# M221D.net
KiCad netlist of a schematic drawn in EAGLE
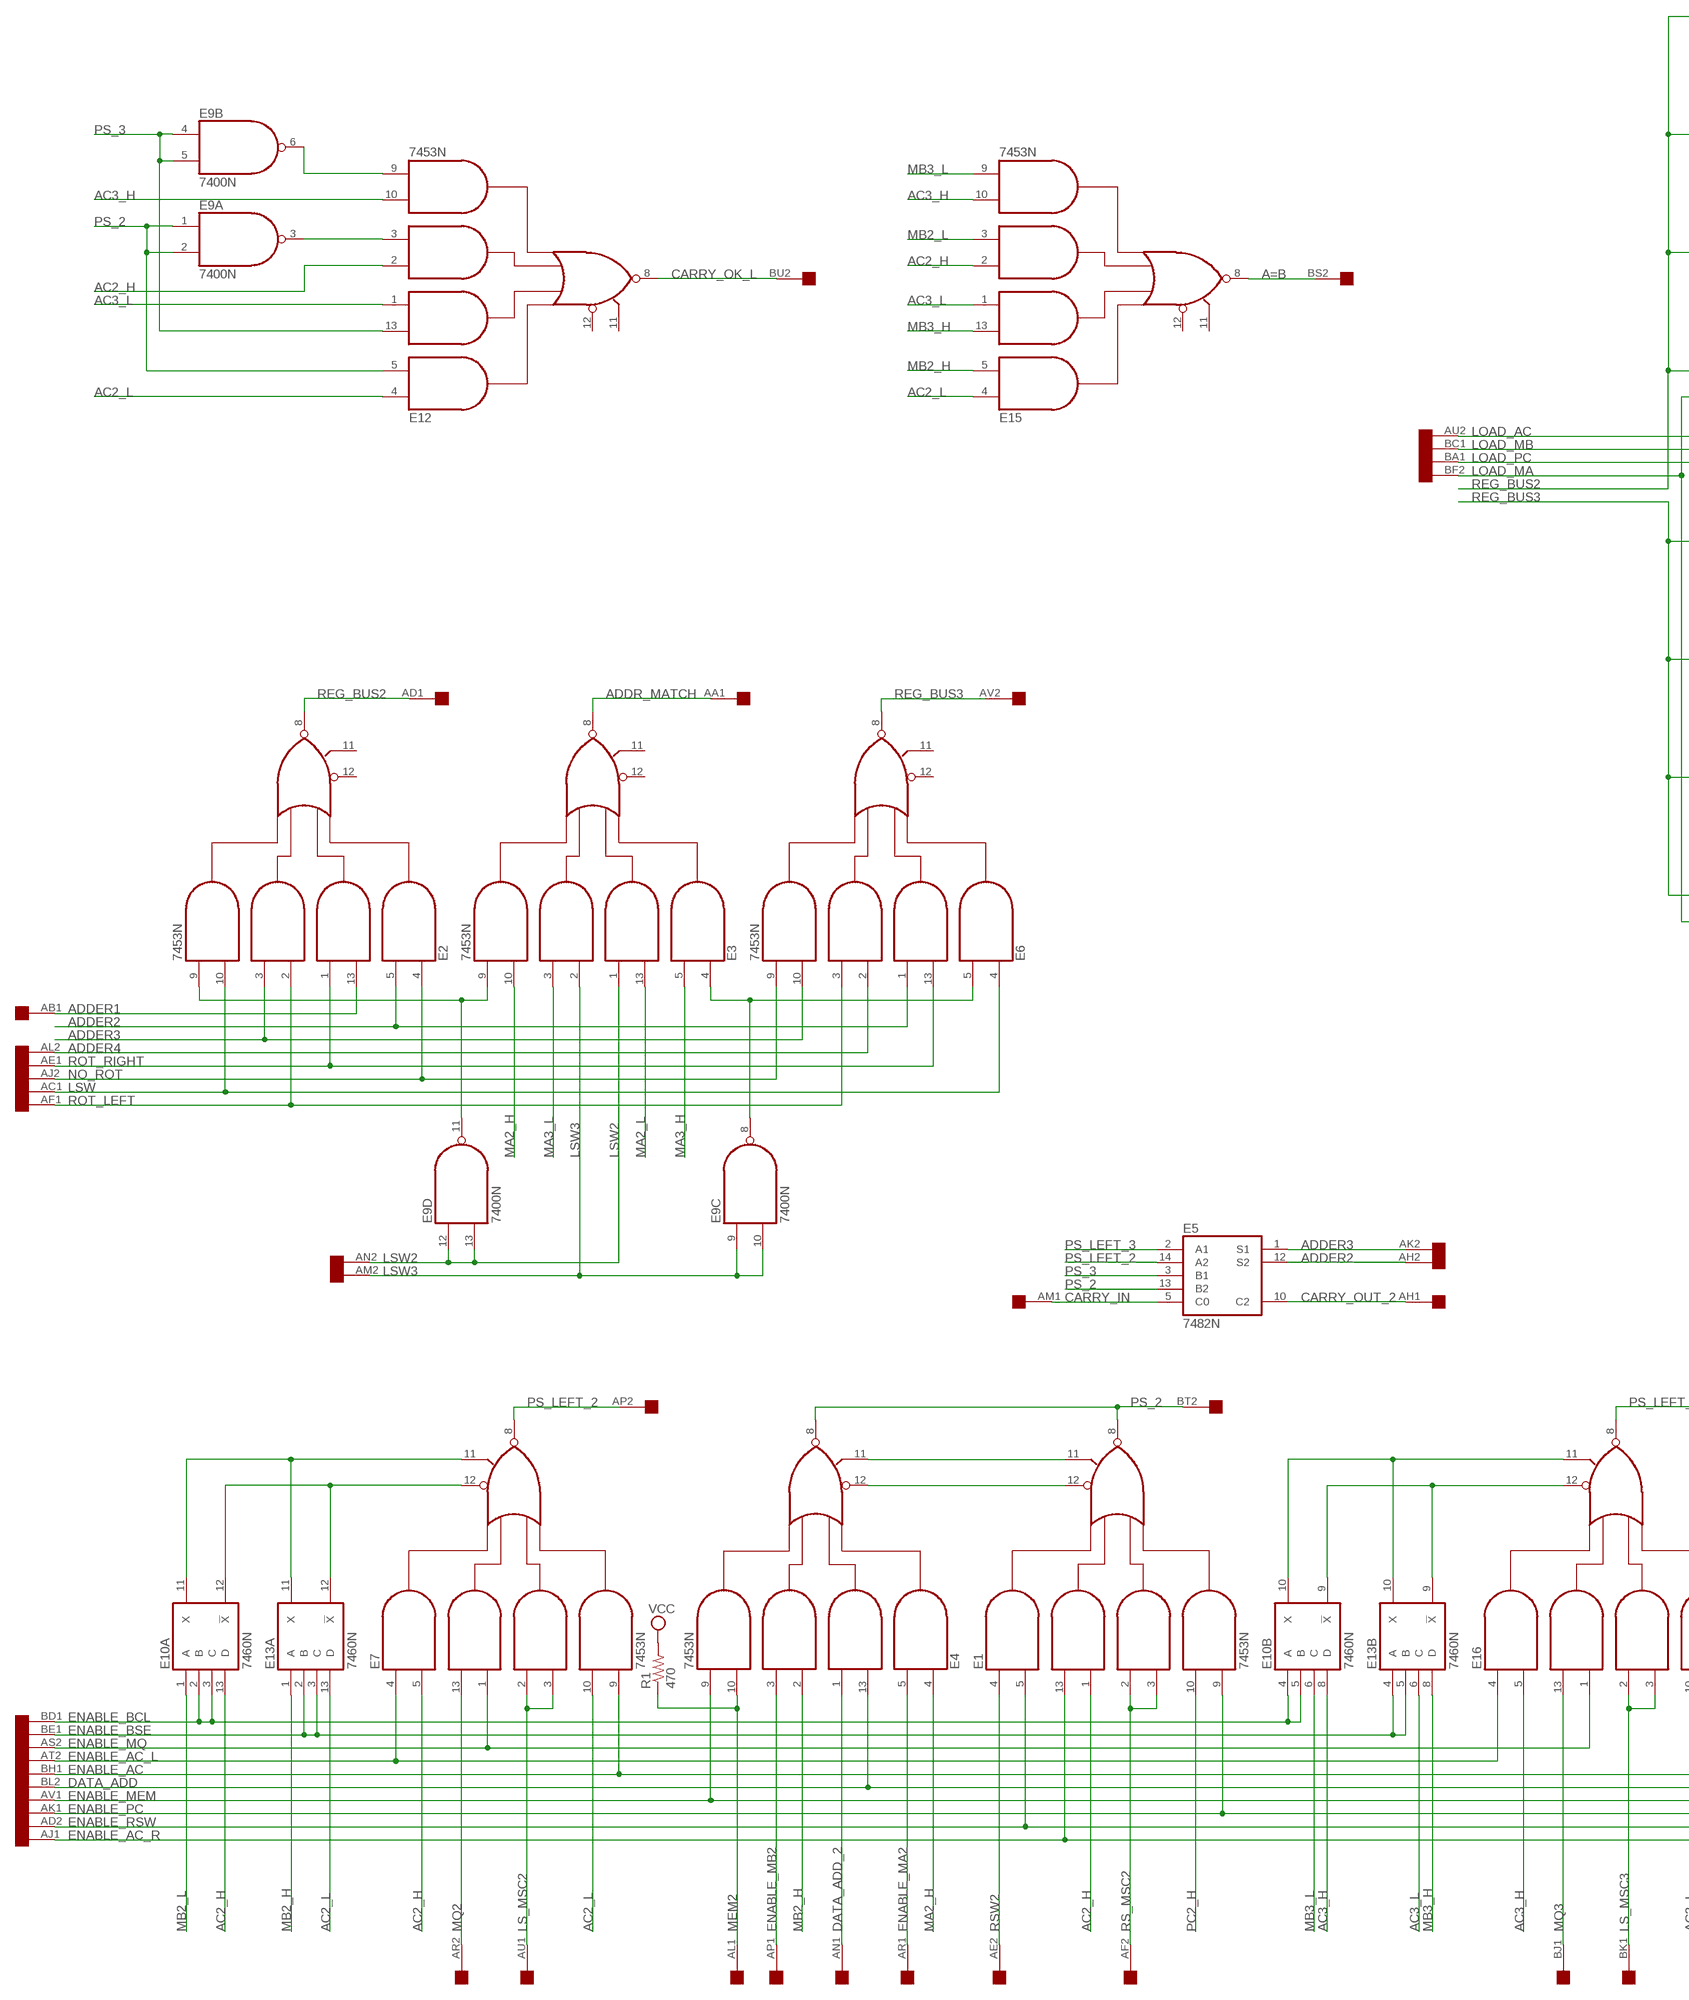
[diagram p0: schematic, sheet 1, part 1 of 2]
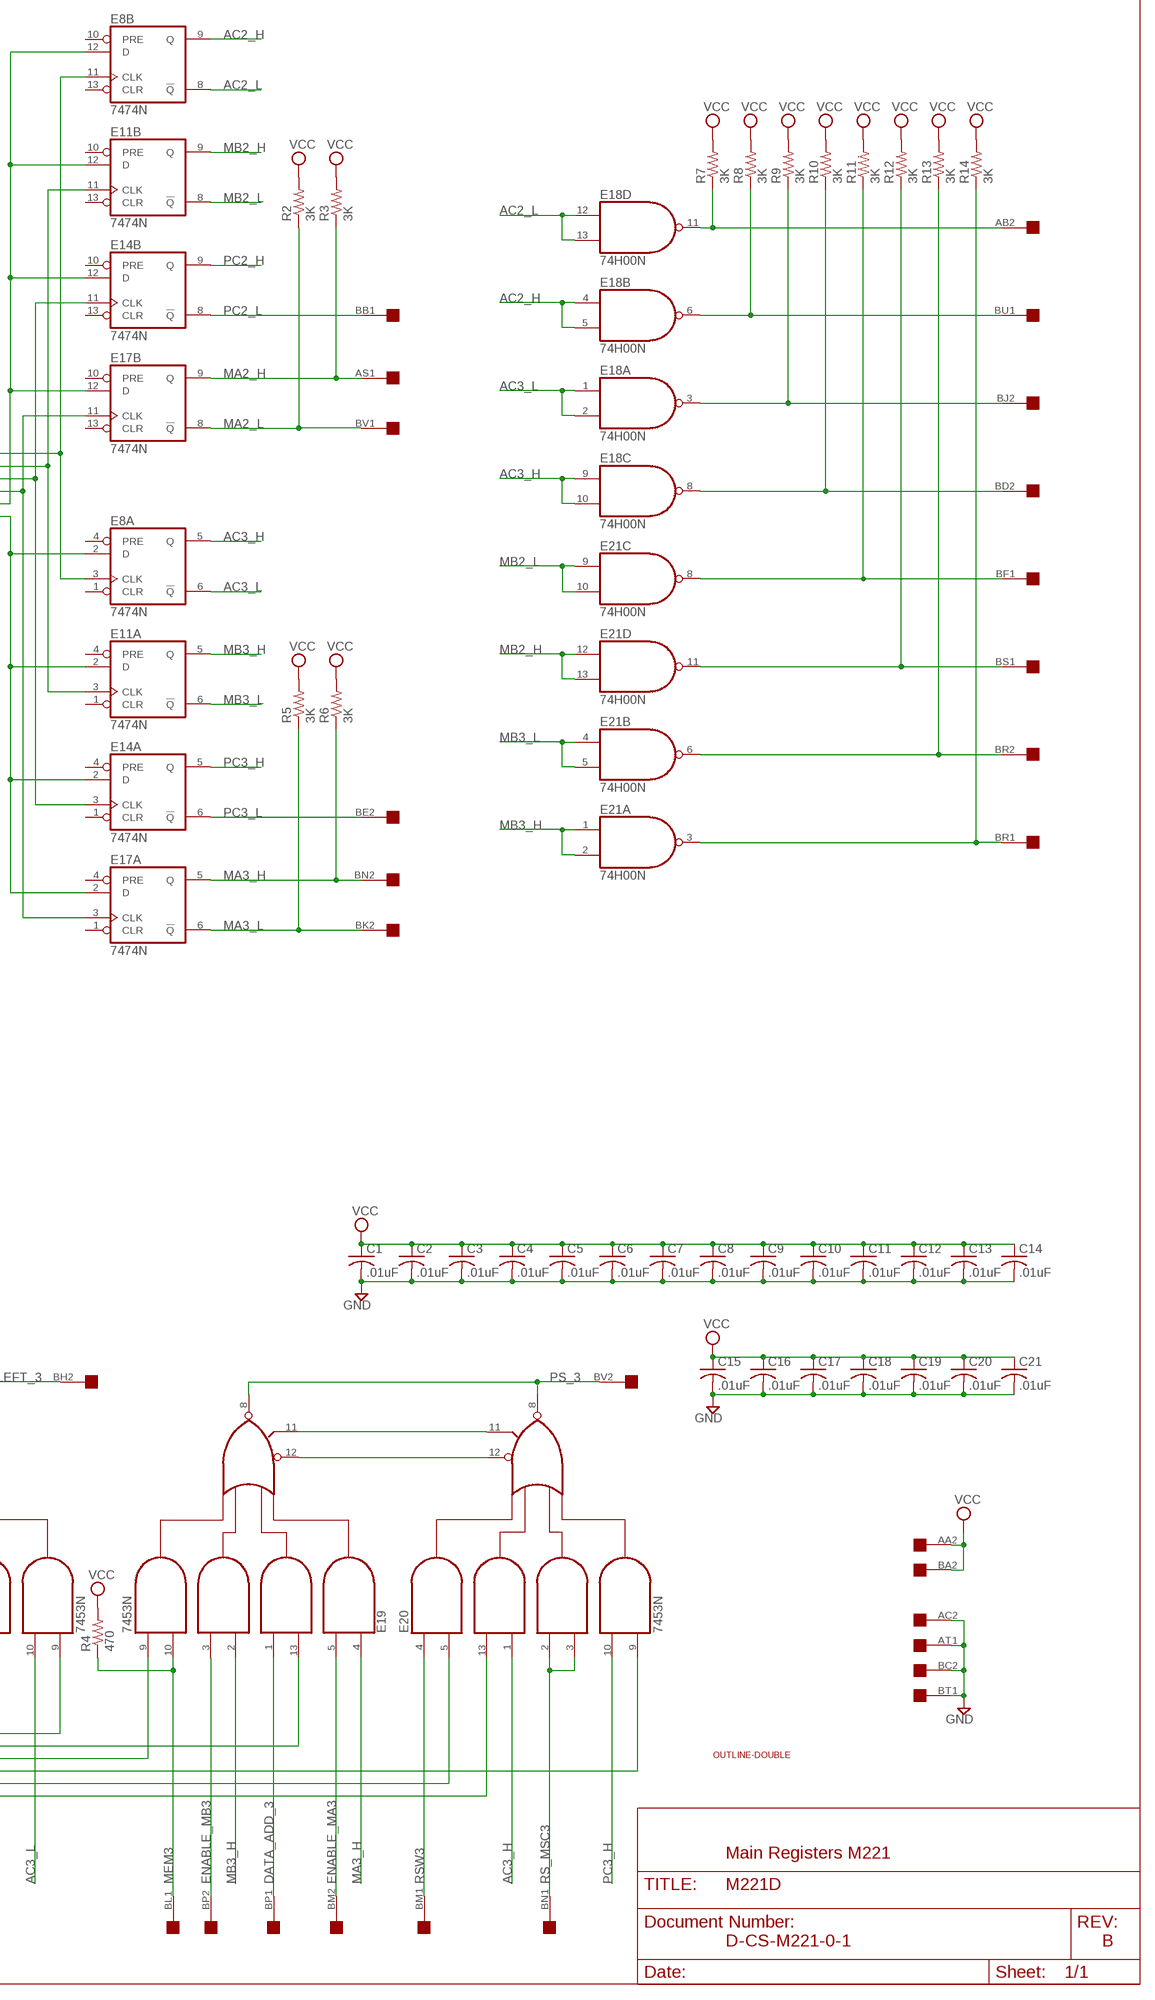
[diagram p1: schematic, sheet 1, part 2 of 2]

(export (version "E")
  (design (tool "Eeschema 10.0.6"))
  (components
    (comp (ref "C1")
      (value ".01uF")
      (footprint "eagle-import:C050-025X075")
      (libsource (lib "eagle-import") (part "C-US050-025X075"))
    )
    (comp (ref "C2")
      (value ".01uF")
      (footprint "eagle-import:C050-025X075")
      (libsource (lib "eagle-import") (part "C-US050-025X075"))
    )
    (comp (ref "C3")
      (value ".01uF")
      (footprint "eagle-import:C050-025X075")
      (libsource (lib "eagle-import") (part "C-US050-025X075"))
    )
    (comp (ref "C4")
      (value ".01uF")
      (footprint "eagle-import:C050-025X075")
      (libsource (lib "eagle-import") (part "C-US050-025X075"))
    )
    (comp (ref "C5")
      (value ".01uF")
      (footprint "eagle-import:C050-025X075")
      (libsource (lib "eagle-import") (part "C-US050-025X075"))
    )
    (comp (ref "C6")
      (value ".01uF")
      (footprint "eagle-import:C050-025X075")
      (libsource (lib "eagle-import") (part "C-US050-025X075"))
    )
    (comp (ref "C7")
      (value ".01uF")
      (footprint "eagle-import:C050-025X075")
      (libsource (lib "eagle-import") (part "C-US050-025X075"))
    )
    (comp (ref "C8")
      (value ".01uF")
      (footprint "eagle-import:C050-025X075")
      (libsource (lib "eagle-import") (part "C-US050-025X075"))
    )
    (comp (ref "C9")
      (value ".01uF")
      (footprint "eagle-import:C050-025X075")
      (libsource (lib "eagle-import") (part "C-US050-025X075"))
    )
    (comp (ref "C10")
      (value ".01uF")
      (footprint "eagle-import:C050-025X075")
      (libsource (lib "eagle-import") (part "C-US050-025X075"))
    )
    (comp (ref "C11")
      (value ".01uF")
      (footprint "eagle-import:C050-025X075")
      (libsource (lib "eagle-import") (part "C-US050-025X075"))
    )
    (comp (ref "C12")
      (value ".01uF")
      (footprint "eagle-import:C050-025X075")
      (libsource (lib "eagle-import") (part "C-US050-025X075"))
    )
    (comp (ref "C13")
      (value ".01uF")
      (footprint "eagle-import:C050-025X075")
      (libsource (lib "eagle-import") (part "C-US050-025X075"))
    )
    (comp (ref "C14")
      (value ".01uF")
      (footprint "eagle-import:C050-025X075")
      (libsource (lib "eagle-import") (part "C-US050-025X075"))
    )
    (comp (ref "C15")
      (value ".01uF")
      (footprint "eagle-import:C050-025X075")
      (libsource (lib "eagle-import") (part "C-US050-025X075"))
    )
    (comp (ref "C16")
      (value ".01uF")
      (footprint "eagle-import:C050-025X075")
      (libsource (lib "eagle-import") (part "C-US050-025X075"))
    )
    (comp (ref "C17")
      (value ".01uF")
      (footprint "eagle-import:C050-025X075")
      (libsource (lib "eagle-import") (part "C-US050-025X075"))
    )
    (comp (ref "C18")
      (value ".01uF")
      (footprint "eagle-import:C050-025X075")
      (libsource (lib "eagle-import") (part "C-US050-025X075"))
    )
    (comp (ref "C19")
      (value ".01uF")
      (footprint "eagle-import:C050-025X075")
      (libsource (lib "eagle-import") (part "C-US050-025X075"))
    )
    (comp (ref "C20")
      (value ".01uF")
      (footprint "eagle-import:C050-025X075")
      (libsource (lib "eagle-import") (part "C-US050-025X075"))
    )
    (comp (ref "C21")
      (value ".01uF")
      (footprint "eagle-import:C050-025X075")
      (libsource (lib "eagle-import") (part "C-US050-025X075"))
    )
    (comp (ref "E1")
      (value "7453N")
      (footprint "eagle-import:DIL14")
      (libsource (lib "eagle-import") (part "7453N"))
    )
    (comp (ref "E2")
      (value "7453N")
      (footprint "eagle-import:DIL14")
      (libsource (lib "eagle-import") (part "7453N"))
    )
    (comp (ref "E3")
      (value "7453N")
      (footprint "eagle-import:DIL14")
      (libsource (lib "eagle-import") (part "7453N"))
    )
    (comp (ref "E4")
      (value "7453N")
      (footprint "eagle-import:DIL14")
      (libsource (lib "eagle-import") (part "7453N"))
    )
    (comp (ref "E5")
      (value "7482N")
      (footprint "eagle-import:DIL14")
      (libsource (lib "eagle-import") (part "7482N"))
    )
    (comp (ref "E6")
      (value "7453N")
      (footprint "eagle-import:DIL14")
      (libsource (lib "eagle-import") (part "7453N"))
    )
    (comp (ref "E7")
      (value "7453N")
      (footprint "eagle-import:DIL14")
      (libsource (lib "eagle-import") (part "7453N"))
    )
    (comp (ref "E8")
      (value "7474N")
      (footprint "eagle-import:DIL14")
      (libsource (lib "eagle-import") (part "7474NS"))
    )
    (comp (ref "E9")
      (value "7400N")
      (footprint "eagle-import:DIL14")
      (libsource (lib "eagle-import") (part "7400N"))
    )
    (comp (ref "E10")
      (value "7460N")
      (footprint "eagle-import:DIL14")
      (libsource (lib "eagle-import") (part "7460N"))
    )
    (comp (ref "E11")
      (value "7474N")
      (footprint "eagle-import:DIL14")
      (libsource (lib "eagle-import") (part "7474NS"))
    )
    (comp (ref "E12")
      (value "7453N")
      (footprint "eagle-import:DIL14")
      (libsource (lib "eagle-import") (part "7453N"))
    )
    (comp (ref "E13")
      (value "7460N")
      (footprint "eagle-import:DIL14")
      (libsource (lib "eagle-import") (part "7460N"))
    )
    (comp (ref "E14")
      (value "7474N")
      (footprint "eagle-import:DIL14")
      (libsource (lib "eagle-import") (part "7474NS"))
    )
    (comp (ref "E15")
      (value "7453N")
      (footprint "eagle-import:DIL14")
      (libsource (lib "eagle-import") (part "7453N"))
    )
    (comp (ref "E16")
      (value "7453N")
      (footprint "eagle-import:DIL14")
      (libsource (lib "eagle-import") (part "7453N"))
    )
    (comp (ref "E17")
      (value "7474N")
      (footprint "eagle-import:DIL14")
      (libsource (lib "eagle-import") (part "7474NS"))
    )
    (comp (ref "E18")
      (value "74H00N")
      (footprint "eagle-import:DIL14")
      (libsource (lib "eagle-import") (part "7400N"))
    )
    (comp (ref "E19")
      (value "7453N")
      (footprint "eagle-import:DIL14")
      (libsource (lib "eagle-import") (part "7453N"))
    )
    (comp (ref "E20")
      (value "7453N")
      (footprint "eagle-import:DIL14")
      (libsource (lib "eagle-import") (part "7453N"))
    )
    (comp (ref "E21")
      (value "74H00N")
      (footprint "eagle-import:DIL14")
      (libsource (lib "eagle-import") (part "7400N"))
    )
    (comp (ref "R1")
      (value "470")
      (footprint "eagle-import:0207_10")
      (libsource (lib "eagle-import") (part "R-US_0207/10"))
    )
    (comp (ref "R2")
      (value "3K")
      (footprint "eagle-import:0207_10")
      (libsource (lib "eagle-import") (part "R-US_0207/10"))
    )
    (comp (ref "R3")
      (value "3K")
      (footprint "eagle-import:0207_10")
      (libsource (lib "eagle-import") (part "R-US_0207/10"))
    )
    (comp (ref "R4")
      (value "470")
      (footprint "eagle-import:0207_10")
      (libsource (lib "eagle-import") (part "R-US_0207/10"))
    )
    (comp (ref "R5")
      (value "3K")
      (footprint "eagle-import:0207_10")
      (libsource (lib "eagle-import") (part "R-US_0207/10"))
    )
    (comp (ref "R6")
      (value "3K")
      (footprint "eagle-import:0207_10")
      (libsource (lib "eagle-import") (part "R-US_0207/10"))
    )
    (comp (ref "R7")
      (value "3K")
      (footprint "eagle-import:0207_10")
      (libsource (lib "eagle-import") (part "R-US_0207/10"))
    )
    (comp (ref "R8")
      (value "3K")
      (footprint "eagle-import:0207_10")
      (libsource (lib "eagle-import") (part "R-US_0207/10"))
    )
    (comp (ref "R9")
      (value "3K")
      (footprint "eagle-import:0207_10")
      (libsource (lib "eagle-import") (part "R-US_0207/10"))
    )
    (comp (ref "R10")
      (value "3K")
      (footprint "eagle-import:0207_10")
      (libsource (lib "eagle-import") (part "R-US_0207/10"))
    )
    (comp (ref "R11")
      (value "3K")
      (footprint "eagle-import:0207_10")
      (libsource (lib "eagle-import") (part "R-US_0207/10"))
    )
    (comp (ref "R12")
      (value "3K")
      (footprint "eagle-import:0207_10")
      (libsource (lib "eagle-import") (part "R-US_0207/10"))
    )
    (comp (ref "R13")
      (value "3K")
      (footprint "eagle-import:0207_10")
      (libsource (lib "eagle-import") (part "R-US_0207/10"))
    )
    (comp (ref "R14")
      (value "3K")
      (footprint "eagle-import:0207_10")
      (libsource (lib "eagle-import") (part "R-US_0207/10"))
    )
    (comp (ref "U$1")
      (value "DOUBLE")
      (footprint "eagle-import:EDGE-CON4")
      (libsource (lib "eagle-import") (part "DOUBLE"))
    )
    (comp (ref "U$2")
      (value "OUTLINE-DOUBLE")
      (footprint "eagle-import:DOUBLE")
      (libsource (lib "eagle-import") (part "OUTLINE-DOUBLE"))
    )
  )
  (nets
    (net (code "1") (name "/A=B") (class "Default")
      (node (ref "E15") (pin "8") (pinfunction "O_8") (pintype "output"))
      (node (ref "U$1") (pin "BS2") (pinfunction "1_BS2") (pintype "bidirectional"))
    )
    (net (code "2") (name "/AC2_H") (class "Default")
      (node (ref "E1") (pin "1") (pinfunction "I4_1") (pintype "input"))
      (node (ref "E10") (pin "13") (pinfunction "D_13") (pintype "input"))
      (node (ref "E12") (pin "2") (pinfunction "I5_2") (pintype "input"))
      (node (ref "E15") (pin "2") (pinfunction "I5_2") (pintype "input"))
      (node (ref "E18") (pin "4") (pinfunction "I0_4") (pintype "input"))
      (node (ref "E18") (pin "5") (pinfunction "I1_5") (pintype "input"))
      (node (ref "E7") (pin "5") (pinfunction "I2_5") (pintype "input"))
      (node (ref "E8") (pin "9") (pinfunction "Q_9") (pintype "output"))
    )
    (net (code "3") (name "/AC2_L") (class "Default")
      (node (ref "E12") (pin "4") (pinfunction "I1_4") (pintype "input"))
      (node (ref "E13") (pin "13") (pinfunction "D_13") (pintype "input"))
      (node (ref "E15") (pin "4") (pinfunction "I1_4") (pintype "input"))
      (node (ref "E18") (pin "12") (pinfunction "I0_12") (pintype "input"))
      (node (ref "E18") (pin "13") (pinfunction "I1_13") (pintype "input"))
      (node (ref "E7") (pin "10") (pinfunction "I7_10") (pintype "input"))
      (node (ref "E8") (pin "8") (pinfunction "~{Q}_8") (pintype "output"))
    )
    (net (code "4") (name "/AC3_H") (class "Default")
      (node (ref "E10") (pin "8") (pinfunction "D_8") (pintype "input"))
      (node (ref "E12") (pin "10") (pinfunction "I7_10") (pintype "input"))
      (node (ref "E15") (pin "10") (pinfunction "I7_10") (pintype "input"))
      (node (ref "E16") (pin "5") (pinfunction "I2_5") (pintype "input"))
      (node (ref "E18") (pin "10") (pinfunction "I1_10") (pintype "input"))
      (node (ref "E18") (pin "9") (pinfunction "I0_9") (pintype "input"))
      (node (ref "E20") (pin "1") (pinfunction "I4_1") (pintype "input"))
      (node (ref "E8") (pin "5") (pinfunction "Q_5") (pintype "output"))
    )
    (net (code "5") (name "/AC3_L") (class "Default")
      (node (ref "E12") (pin "1") (pinfunction "I4_1") (pintype "input"))
      (node (ref "E13") (pin "6") (pinfunction "C_6") (pintype "input"))
      (node (ref "E15") (pin "1") (pinfunction "I4_1") (pintype "input"))
      (node (ref "E16") (pin "10") (pinfunction "I7_10") (pintype "input"))
      (node (ref "E18") (pin "1") (pinfunction "I0_1") (pintype "input"))
      (node (ref "E18") (pin "2") (pinfunction "I1_2") (pintype "input"))
      (node (ref "E8") (pin "6") (pinfunction "~{Q}_6") (pintype "output"))
    )
    (net (code "6") (name "/ADDER1") (class "Default")
      (node (ref "E2") (pin "13") (pinfunction "I3_13") (pintype "input"))
      (node (ref "U$1") (pin "AB1") (pinfunction "1_AB1") (pintype "bidirectional"))
    )
    (net (code "7") (name "/ADDER2") (class "Default")
      (node (ref "E2") (pin "5") (pinfunction "I2_5") (pintype "input"))
      (node (ref "E5") (pin "12") (pinfunction "S2_12") (pintype "output"))
      (node (ref "E6") (pin "1") (pinfunction "I4_1") (pintype "input"))
      (node (ref "U$1") (pin "AH2") (pinfunction "1_AH2") (pintype "bidirectional"))
    )
    (net (code "8") (name "/ADDER3") (class "Default")
      (node (ref "E2") (pin "3") (pinfunction "I6_3") (pintype "input"))
      (node (ref "E5") (pin "1") (pinfunction "S1_1") (pintype "output"))
      (node (ref "E6") (pin "10") (pinfunction "I7_10") (pintype "input"))
      (node (ref "U$1") (pin "AK2") (pinfunction "1_AK2") (pintype "bidirectional"))
    )
    (net (code "9") (name "/ADDER4") (class "Default")
      (node (ref "E6") (pin "2") (pinfunction "I5_2") (pintype "input"))
      (node (ref "U$1") (pin "AL2") (pinfunction "1_AL2") (pintype "bidirectional"))
    )
    (net (code "10") (name "/ADDR_MATCH") (class "Default")
      (node (ref "E3") (pin "8") (pinfunction "O_8") (pintype "output"))
      (node (ref "U$1") (pin "AA1") (pinfunction "1_AA1") (pintype "bidirectional"))
    )
    (net (code "11") (name "/CARRY_IN") (class "Default")
      (node (ref "E5") (pin "5") (pinfunction "C0_5") (pintype "input"))
      (node (ref "U$1") (pin "AM1") (pinfunction "1_AM1") (pintype "bidirectional"))
    )
    (net (code "12") (name "/CARRY_OK_L") (class "Default")
      (node (ref "E12") (pin "8") (pinfunction "O_8") (pintype "output"))
      (node (ref "U$1") (pin "BU2") (pinfunction "1_BU2") (pintype "bidirectional"))
    )
    (net (code "13") (name "/CARRY_OUT_2") (class "Default")
      (node (ref "E5") (pin "10") (pinfunction "C2_10") (pintype "output"))
      (node (ref "U$1") (pin "AH1") (pinfunction "1_AH1") (pintype "bidirectional"))
    )
    (net (code "14") (name "/DATA_ADD") (class "Default")
      (node (ref "E19") (pin "13") (pinfunction "I3_13") (pintype "input"))
      (node (ref "E4") (pin "13") (pinfunction "I3_13") (pintype "input"))
      (node (ref "U$1") (pin "BL2") (pinfunction "1_BL2") (pintype "bidirectional"))
    )
    (net (code "15") (name "/DATA_ADD_2") (class "Default")
      (node (ref "E4") (pin "1") (pinfunction "I4_1") (pintype "input"))
      (node (ref "U$1") (pin "AN1") (pinfunction "1_AN1") (pintype "bidirectional"))
    )
    (net (code "16") (name "/DATA_ADD_3") (class "Default")
      (node (ref "E19") (pin "1") (pinfunction "I4_1") (pintype "input"))
      (node (ref "U$1") (pin "BP1") (pinfunction "1_BP1") (pintype "bidirectional"))
    )
    (net (code "17") (name "/ENABLE_AC") (class "Default")
      (node (ref "E16") (pin "9") (pinfunction "I8_9") (pintype "input"))
      (node (ref "E7") (pin "9") (pinfunction "I8_9") (pintype "input"))
      (node (ref "U$1") (pin "BH1") (pinfunction "1_BH1") (pintype "bidirectional"))
    )
    (net (code "18") (name "/ENABLE_AC_L") (class "Default")
      (node (ref "E16") (pin "4") (pinfunction "I1_4") (pintype "input"))
      (node (ref "E7") (pin "4") (pinfunction "I1_4") (pintype "input"))
      (node (ref "U$1") (pin "AT2") (pinfunction "1_AT2") (pintype "bidirectional"))
    )
    (net (code "19") (name "/ENABLE_AC_R") (class "Default")
      (node (ref "E1") (pin "13") (pinfunction "I3_13") (pintype "input"))
      (node (ref "E20") (pin "13") (pinfunction "I3_13") (pintype "input"))
      (node (ref "U$1") (pin "AJ1") (pinfunction "1_AJ1") (pintype "bidirectional"))
    )
    (net (code "20") (name "/ENABLE_BCL") (class "Default")
      (node (ref "E10") (pin "2") (pinfunction "B_2") (pintype "input"))
      (node (ref "E10") (pin "3") (pinfunction "C_3") (pintype "input"))
      (node (ref "E10") (pin "4") (pinfunction "A_4") (pintype "input"))
      (node (ref "E10") (pin "5") (pinfunction "B_5") (pintype "input"))
      (node (ref "U$1") (pin "BD1") (pinfunction "1_BD1") (pintype "bidirectional"))
    )
    (net (code "21") (name "/ENABLE_BSE") (class "Default")
      (node (ref "E13") (pin "2") (pinfunction "B_2") (pintype "input"))
      (node (ref "E13") (pin "3") (pinfunction "C_3") (pintype "input"))
      (node (ref "E13") (pin "4") (pinfunction "A_4") (pintype "input"))
      (node (ref "E13") (pin "5") (pinfunction "B_5") (pintype "input"))
      (node (ref "U$1") (pin "BE1") (pinfunction "1_BE1") (pintype "bidirectional"))
    )
    (net (code "22") (name "/ENABLE_MA2") (class "Default")
      (node (ref "E4") (pin "5") (pinfunction "I2_5") (pintype "input"))
      (node (ref "U$1") (pin "AR1") (pinfunction "1_AR1") (pintype "bidirectional"))
    )
    (net (code "23") (name "/ENABLE_MA3") (class "Default")
      (node (ref "E19") (pin "5") (pinfunction "I2_5") (pintype "input"))
      (node (ref "U$1") (pin "BM2") (pinfunction "1_BM2") (pintype "bidirectional"))
    )
    (net (code "24") (name "/ENABLE_MB2") (class "Default")
      (node (ref "E4") (pin "3") (pinfunction "I6_3") (pintype "input"))
      (node (ref "U$1") (pin "AP1") (pinfunction "1_AP1") (pintype "bidirectional"))
    )
    (net (code "25") (name "/ENABLE_MB3") (class "Default")
      (node (ref "E19") (pin "3") (pinfunction "I6_3") (pintype "input"))
      (node (ref "U$1") (pin "BP2") (pinfunction "1_BP2") (pintype "bidirectional"))
    )
    (net (code "26") (name "/ENABLE_MEM") (class "Default")
      (node (ref "E19") (pin "9") (pinfunction "I8_9") (pintype "input"))
      (node (ref "E4") (pin "9") (pinfunction "I8_9") (pintype "input"))
      (node (ref "U$1") (pin "AV1") (pinfunction "1_AV1") (pintype "bidirectional"))
    )
    (net (code "27") (name "/ENABLE_MQ") (class "Default")
      (node (ref "E16") (pin "1") (pinfunction "I4_1") (pintype "input"))
      (node (ref "E7") (pin "1") (pinfunction "I4_1") (pintype "input"))
      (node (ref "U$1") (pin "AS2") (pinfunction "1_AS2") (pintype "bidirectional"))
    )
    (net (code "28") (name "/ENABLE_PC") (class "Default")
      (node (ref "E1") (pin "9") (pinfunction "I8_9") (pintype "input"))
      (node (ref "E20") (pin "9") (pinfunction "I8_9") (pintype "input"))
      (node (ref "U$1") (pin "AK1") (pinfunction "1_AK1") (pintype "bidirectional"))
    )
    (net (code "29") (name "/ENABLE_RSW") (class "Default")
      (node (ref "E1") (pin "5") (pinfunction "I2_5") (pintype "input"))
      (node (ref "E20") (pin "5") (pinfunction "I2_5") (pintype "input"))
      (node (ref "U$1") (pin "AD2") (pinfunction "1_AD2") (pintype "bidirectional"))
    )
    (net (code "30") (name "/LOAD_AC") (class "Default")
      (node (ref "E8") (pin "11") (pinfunction "CLK_11") (pintype "input"))
      (node (ref "E8") (pin "3") (pinfunction "CLK_3") (pintype "input"))
      (node (ref "U$1") (pin "AU2") (pinfunction "1_AU2") (pintype "bidirectional"))
    )
    (net (code "31") (name "/LOAD_MA") (class "Default")
      (node (ref "E17") (pin "11") (pinfunction "CLK_11") (pintype "input"))
      (node (ref "E17") (pin "3") (pinfunction "CLK_3") (pintype "input"))
      (node (ref "U$1") (pin "BF2") (pinfunction "1_BF2") (pintype "bidirectional"))
    )
    (net (code "32") (name "/LOAD_MB") (class "Default")
      (node (ref "E11") (pin "11") (pinfunction "CLK_11") (pintype "input"))
      (node (ref "E11") (pin "3") (pinfunction "CLK_3") (pintype "input"))
      (node (ref "U$1") (pin "BC1") (pinfunction "1_BC1") (pintype "bidirectional"))
    )
    (net (code "33") (name "/LOAD_PC") (class "Default")
      (node (ref "E14") (pin "11") (pinfunction "CLK_11") (pintype "input"))
      (node (ref "E14") (pin "3") (pinfunction "CLK_3") (pintype "input"))
      (node (ref "U$1") (pin "BA1") (pinfunction "1_BA1") (pintype "bidirectional"))
    )
    (net (code "34") (name "/LSW") (class "Default")
      (node (ref "E2") (pin "10") (pinfunction "I7_10") (pintype "input"))
      (node (ref "E6") (pin "4") (pinfunction "I1_4") (pintype "input"))
      (node (ref "U$1") (pin "AC1") (pinfunction "1_AC1") (pintype "bidirectional"))
    )
    (net (code "35") (name "/LSW2") (class "Default")
      (node (ref "E3") (pin "1") (pinfunction "I4_1") (pintype "input"))
      (node (ref "E9") (pin "12") (pinfunction "I0_12") (pintype "input"))
      (node (ref "E9") (pin "13") (pinfunction "I1_13") (pintype "input"))
      (node (ref "U$1") (pin "AN2") (pinfunction "1_AN2") (pintype "bidirectional"))
    )
    (net (code "36") (name "/LSW3") (class "Default")
      (node (ref "E3") (pin "2") (pinfunction "I5_2") (pintype "input"))
      (node (ref "E9") (pin "10") (pinfunction "I1_10") (pintype "input"))
      (node (ref "E9") (pin "9") (pinfunction "I0_9") (pintype "input"))
      (node (ref "U$1") (pin "AM2") (pinfunction "1_AM2") (pintype "bidirectional"))
    )
    (net (code "37") (name "/LS_MSC2") (class "Default")
      (node (ref "E7") (pin "2") (pinfunction "I5_2") (pintype "input"))
      (node (ref "E7") (pin "3") (pinfunction "I6_3") (pintype "input"))
      (node (ref "U$1") (pin "AU1") (pinfunction "1_AU1") (pintype "bidirectional"))
    )
    (net (code "38") (name "/LS_MSC3") (class "Default")
      (node (ref "E16") (pin "2") (pinfunction "I5_2") (pintype "input"))
      (node (ref "E16") (pin "3") (pinfunction "I6_3") (pintype "input"))
      (node (ref "U$1") (pin "BK1") (pinfunction "1_BK1") (pintype "bidirectional"))
    )
    (net (code "39") (name "/MA2_H") (class "Default")
      (node (ref "E17") (pin "9") (pinfunction "Q_9") (pintype "output"))
      (node (ref "E3") (pin "10") (pinfunction "I7_10") (pintype "input"))
      (node (ref "E4") (pin "4") (pinfunction "I1_4") (pintype "input"))
      (node (ref "R3") (pin "1") (pinfunction "1_1") (pintype "passive"))
      (node (ref "U$1") (pin "AS1") (pinfunction "1_AS1") (pintype "bidirectional"))
    )
    (net (code "40") (name "/MA2_L") (class "Default")
      (node (ref "E17") (pin "8") (pinfunction "~{Q}_8") (pintype "output"))
      (node (ref "E3") (pin "13") (pinfunction "I3_13") (pintype "input"))
      (node (ref "R2") (pin "1") (pinfunction "1_1") (pintype "passive"))
      (node (ref "U$1") (pin "BV1") (pinfunction "1_BV1") (pintype "bidirectional"))
    )
    (net (code "41") (name "/MA3_H") (class "Default")
      (node (ref "E17") (pin "5") (pinfunction "Q_5") (pintype "output"))
      (node (ref "E19") (pin "4") (pinfunction "I1_4") (pintype "input"))
      (node (ref "E3") (pin "5") (pinfunction "I2_5") (pintype "input"))
      (node (ref "R6") (pin "1") (pinfunction "1_1") (pintype "passive"))
      (node (ref "U$1") (pin "BN2") (pinfunction "1_BN2") (pintype "bidirectional"))
    )
    (net (code "42") (name "/MA3_L") (class "Default")
      (node (ref "E17") (pin "6") (pinfunction "~{Q}_6") (pintype "output"))
      (node (ref "E3") (pin "3") (pinfunction "I6_3") (pintype "input"))
      (node (ref "R5") (pin "1") (pinfunction "1_1") (pintype "passive"))
      (node (ref "U$1") (pin "BK2") (pinfunction "1_BK2") (pintype "bidirectional"))
    )
    (net (code "43") (name "/MB2_H") (class "Default")
      (node (ref "E11") (pin "9") (pinfunction "Q_9") (pintype "output"))
      (node (ref "E13") (pin "1") (pinfunction "A_1") (pintype "input"))
      (node (ref "E15") (pin "5") (pinfunction "I2_5") (pintype "input"))
      (node (ref "E21") (pin "12") (pinfunction "I0_12") (pintype "input"))
      (node (ref "E21") (pin "13") (pinfunction "I1_13") (pintype "input"))
      (node (ref "E4") (pin "2") (pinfunction "I5_2") (pintype "input"))
    )
    (net (code "44") (name "/MB2_L") (class "Default")
      (node (ref "E10") (pin "1") (pinfunction "A_1") (pintype "input"))
      (node (ref "E11") (pin "8") (pinfunction "~{Q}_8") (pintype "output"))
      (node (ref "E15") (pin "3") (pinfunction "I6_3") (pintype "input"))
      (node (ref "E21") (pin "10") (pinfunction "I1_10") (pintype "input"))
      (node (ref "E21") (pin "9") (pinfunction "I0_9") (pintype "input"))
    )
    (net (code "45") (name "/MB3_H") (class "Default")
      (node (ref "E11") (pin "5") (pinfunction "Q_5") (pintype "output"))
      (node (ref "E13") (pin "8") (pinfunction "D_8") (pintype "input"))
      (node (ref "E15") (pin "13") (pinfunction "I3_13") (pintype "input"))
      (node (ref "E19") (pin "2") (pinfunction "I5_2") (pintype "input"))
      (node (ref "E21") (pin "1") (pinfunction "I0_1") (pintype "input"))
      (node (ref "E21") (pin "2") (pinfunction "I1_2") (pintype "input"))
    )
    (net (code "46") (name "/MB3_L") (class "Default")
      (node (ref "E10") (pin "6") (pinfunction "C_6") (pintype "input"))
      (node (ref "E11") (pin "6") (pinfunction "~{Q}_6") (pintype "output"))
      (node (ref "E15") (pin "9") (pinfunction "I8_9") (pintype "input"))
      (node (ref "E21") (pin "4") (pinfunction "I0_4") (pintype "input"))
      (node (ref "E21") (pin "5") (pinfunction "I1_5") (pintype "input"))
    )
    (net (code "47") (name "/MEM2") (class "Default")
      (node (ref "E4") (pin "10") (pinfunction "I7_10") (pintype "input"))
      (node (ref "R1") (pin "1") (pinfunction "1_1") (pintype "passive"))
      (node (ref "U$1") (pin "AL1") (pinfunction "1_AL1") (pintype "bidirectional"))
    )
    (net (code "48") (name "/MEM3") (class "Default")
      (node (ref "E19") (pin "10") (pinfunction "I7_10") (pintype "input"))
      (node (ref "R4") (pin "1") (pinfunction "1_1") (pintype "passive"))
      (node (ref "U$1") (pin "BL1") (pinfunction "1_BL1") (pintype "bidirectional"))
    )
    (net (code "49") (name "/MQ2") (class "Default")
      (node (ref "E7") (pin "13") (pinfunction "I3_13") (pintype "input"))
      (node (ref "U$1") (pin "AR2") (pinfunction "1_AR2") (pintype "bidirectional"))
    )
    (net (code "50") (name "/MQ3") (class "Default")
      (node (ref "E16") (pin "13") (pinfunction "I3_13") (pintype "input"))
      (node (ref "U$1") (pin "BJ1") (pinfunction "1_BJ1") (pintype "bidirectional"))
    )
    (net (code "51") (name "/NO_ROT") (class "Default")
      (node (ref "E2") (pin "4") (pinfunction "I1_4") (pintype "input"))
      (node (ref "E6") (pin "9") (pinfunction "I8_9") (pintype "input"))
      (node (ref "U$1") (pin "AJ2") (pinfunction "1_AJ2") (pintype "bidirectional"))
    )
    (net (code "52") (name "/PC2_H") (class "Default")
      (node (ref "E1") (pin "10") (pinfunction "I7_10") (pintype "input"))
      (node (ref "E14") (pin "9") (pinfunction "Q_9") (pintype "output"))
    )
    (net (code "53") (name "/PC2_L") (class "Default")
      (node (ref "E14") (pin "8") (pinfunction "~{Q}_8") (pintype "output"))
      (node (ref "U$1") (pin "BB1") (pinfunction "1_BB1") (pintype "bidirectional"))
    )
    (net (code "54") (name "/PC3_H") (class "Default")
      (node (ref "E14") (pin "5") (pinfunction "Q_5") (pintype "output"))
      (node (ref "E20") (pin "10") (pinfunction "I7_10") (pintype "input"))
    )
    (net (code "55") (name "/PC3_L") (class "Default")
      (node (ref "E14") (pin "6") (pinfunction "~{Q}_6") (pintype "output"))
      (node (ref "U$1") (pin "BE2") (pinfunction "1_BE2") (pintype "bidirectional"))
    )
    (net (code "56") (name "/PS_2") (class "Default")
      (node (ref "E1") (pin "8") (pinfunction "O_8") (pintype "output"))
      (node (ref "E12") (pin "5") (pinfunction "I2_5") (pintype "input"))
      (node (ref "E4") (pin "8") (pinfunction "O_8") (pintype "output"))
      (node (ref "E5") (pin "13") (pinfunction "B2_13") (pintype "input"))
      (node (ref "E9") (pin "1") (pinfunction "I0_1") (pintype "input"))
      (node (ref "E9") (pin "2") (pinfunction "I1_2") (pintype "input"))
      (node (ref "U$1") (pin "BT2") (pinfunction "1_BT2") (pintype "bidirectional"))
    )
    (net (code "57") (name "/PS_3") (class "Default")
      (node (ref "E12") (pin "13") (pinfunction "I3_13") (pintype "input"))
      (node (ref "E19") (pin "8") (pinfunction "O_8") (pintype "output"))
      (node (ref "E20") (pin "8") (pinfunction "O_8") (pintype "output"))
      (node (ref "E5") (pin "3") (pinfunction "B1_3") (pintype "input"))
      (node (ref "E9") (pin "4") (pinfunction "I0_4") (pintype "input"))
      (node (ref "E9") (pin "5") (pinfunction "I1_5") (pintype "input"))
      (node (ref "U$1") (pin "BV2") (pinfunction "1_BV2") (pintype "bidirectional"))
    )
    (net (code "58") (name "/PS_LEFT_2") (class "Default")
      (node (ref "E5") (pin "14") (pinfunction "A2_14") (pintype "input"))
      (node (ref "E7") (pin "8") (pinfunction "O_8") (pintype "output"))
      (node (ref "U$1") (pin "AP2") (pinfunction "1_AP2") (pintype "bidirectional"))
    )
    (net (code "59") (name "/PS_LEFT_3") (class "Default")
      (node (ref "E16") (pin "8") (pinfunction "O_8") (pintype "output"))
      (node (ref "E5") (pin "2") (pinfunction "A1_2") (pintype "input"))
      (node (ref "U$1") (pin "BH2") (pinfunction "1_BH2") (pintype "bidirectional"))
    )
    (net (code "60") (name "/REG_BUS2") (class "Default")
      (node (ref "E11") (pin "12") (pinfunction "D_12") (pintype "input"))
      (node (ref "E14") (pin "12") (pinfunction "D_12") (pintype "input"))
      (node (ref "E17") (pin "12") (pinfunction "D_12") (pintype "input"))
      (node (ref "E2") (pin "8") (pinfunction "O_8") (pintype "output"))
      (node (ref "E8") (pin "12") (pinfunction "D_12") (pintype "input"))
      (node (ref "U$1") (pin "AD1") (pinfunction "1_AD1") (pintype "bidirectional"))
    )
    (net (code "61") (name "/REG_BUS3") (class "Default")
      (node (ref "E11") (pin "2") (pinfunction "D_2") (pintype "input"))
      (node (ref "E14") (pin "2") (pinfunction "D_2") (pintype "input"))
      (node (ref "E17") (pin "2") (pinfunction "D_2") (pintype "input"))
      (node (ref "E6") (pin "8") (pinfunction "O_8") (pintype "output"))
      (node (ref "E8") (pin "2") (pinfunction "D_2") (pintype "input"))
      (node (ref "U$1") (pin "AV2") (pinfunction "1_AV2") (pintype "bidirectional"))
    )
    (net (code "62") (name "/ROT_LEFT") (class "Default")
      (node (ref "E2") (pin "2") (pinfunction "I5_2") (pintype "input"))
      (node (ref "E6") (pin "3") (pinfunction "I6_3") (pintype "input"))
      (node (ref "U$1") (pin "AF1") (pinfunction "1_AF1") (pintype "bidirectional"))
    )
    (net (code "63") (name "/ROT_RIGHT") (class "Default")
      (node (ref "E2") (pin "1") (pinfunction "I4_1") (pintype "input"))
      (node (ref "E6") (pin "13") (pinfunction "I3_13") (pintype "input"))
      (node (ref "U$1") (pin "AE1") (pinfunction "1_AE1") (pintype "bidirectional"))
    )
    (net (code "64") (name "/RSW2") (class "Default")
      (node (ref "E1") (pin "4") (pinfunction "I1_4") (pintype "input"))
      (node (ref "U$1") (pin "AE2") (pinfunction "1_AE2") (pintype "bidirectional"))
    )
    (net (code "65") (name "/RSW3") (class "Default")
      (node (ref "E20") (pin "4") (pinfunction "I1_4") (pintype "input"))
      (node (ref "U$1") (pin "BM1") (pinfunction "1_BM1") (pintype "bidirectional"))
    )
    (net (code "66") (name "/RS_MSC2") (class "Default")
      (node (ref "E1") (pin "2") (pinfunction "I5_2") (pintype "input"))
      (node (ref "E1") (pin "3") (pinfunction "I6_3") (pintype "input"))
      (node (ref "U$1") (pin "AF2") (pinfunction "1_AF2") (pintype "bidirectional"))
    )
    (net (code "67") (name "/RS_MSC3") (class "Default")
      (node (ref "E20") (pin "2") (pinfunction "I5_2") (pintype "input"))
      (node (ref "E20") (pin "3") (pinfunction "I6_3") (pintype "input"))
      (node (ref "U$1") (pin "BN1") (pinfunction "1_BN1") (pintype "bidirectional"))
    )
    (net (code "68") (name "GND") (class "Default")
      (node (ref "C1") (pin "2") (pinfunction "2_2") (pintype "passive"))
      (node (ref "C10") (pin "2") (pinfunction "2_2") (pintype "passive"))
      (node (ref "C11") (pin "2") (pinfunction "2_2") (pintype "passive"))
      (node (ref "C12") (pin "2") (pinfunction "2_2") (pintype "passive"))
      (node (ref "C13") (pin "2") (pinfunction "2_2") (pintype "passive"))
      (node (ref "C14") (pin "2") (pinfunction "2_2") (pintype "passive"))
      (node (ref "C15") (pin "2") (pinfunction "2_2") (pintype "passive"))
      (node (ref "C16") (pin "2") (pinfunction "2_2") (pintype "passive"))
      (node (ref "C17") (pin "2") (pinfunction "2_2") (pintype "passive"))
      (node (ref "C18") (pin "2") (pinfunction "2_2") (pintype "passive"))
      (node (ref "C19") (pin "2") (pinfunction "2_2") (pintype "passive"))
      (node (ref "C2") (pin "2") (pinfunction "2_2") (pintype "passive"))
      (node (ref "C20") (pin "2") (pinfunction "2_2") (pintype "passive"))
      (node (ref "C21") (pin "2") (pinfunction "2_2") (pintype "passive"))
      (node (ref "C3") (pin "2") (pinfunction "2_2") (pintype "passive"))
      (node (ref "C4") (pin "2") (pinfunction "2_2") (pintype "passive"))
      (node (ref "C5") (pin "2") (pinfunction "2_2") (pintype "passive"))
      (node (ref "C6") (pin "2") (pinfunction "2_2") (pintype "passive"))
      (node (ref "C7") (pin "2") (pinfunction "2_2") (pintype "passive"))
      (node (ref "C8") (pin "2") (pinfunction "2_2") (pintype "passive"))
      (node (ref "C9") (pin "2") (pinfunction "2_2") (pintype "passive"))
      (node (ref "U$1") (pin "AC2") (pinfunction "1_AC2") (pintype "bidirectional"))
      (node (ref "U$1") (pin "AT1") (pinfunction "1_AT1") (pintype "bidirectional"))
      (node (ref "U$1") (pin "BC2") (pinfunction "1_BC2") (pintype "bidirectional"))
      (node (ref "U$1") (pin "BT1") (pinfunction "1_BT1") (pintype "bidirectional"))
    )
    (net (code "69") (name "Net-(E1A-I9)") (class "Default")
      (node (ref "E1") (pin "12") (pinfunction "I9_12") (pintype "passive"))
      (node (ref "E4") (pin "12") (pinfunction "I9_12") (pintype "passive"))
    )
    (net (code "70") (name "Net-(E1A-I10)") (class "Default")
      (node (ref "E1") (pin "11") (pinfunction "I10_11") (pintype "passive"))
      (node (ref "E4") (pin "11") (pinfunction "I10_11") (pintype "passive"))
    )
    (net (code "71") (name "Net-(E2A-I8)") (class "Default")
      (node (ref "E2") (pin "9") (pinfunction "I8_9") (pintype "input"))
      (node (ref "E3") (pin "9") (pinfunction "I8_9") (pintype "input"))
      (node (ref "E9") (pin "11") (pinfunction "O_11") (pintype "output"))
    )
    (net (code "72") (name "Net-(E3A-I1)") (class "Default")
      (node (ref "E3") (pin "4") (pinfunction "I1_4") (pintype "input"))
      (node (ref "E6") (pin "5") (pinfunction "I2_5") (pintype "input"))
      (node (ref "E9") (pin "8") (pinfunction "O_8") (pintype "output"))
    )
    (net (code "73") (name "Net-(E10A-X)") (class "Default")
      (node (ref "E10") (pin "11") (pinfunction "X_11") (pintype "output"))
      (node (ref "E13") (pin "11") (pinfunction "X_11") (pintype "output"))
      (node (ref "E7") (pin "11") (pinfunction "I10_11") (pintype "passive"))
    )
    (net (code "74") (name "Net-(E10A-~{X})") (class "Default")
      (node (ref "E10") (pin "12") (pinfunction "~{X}_12") (pintype "output"))
      (node (ref "E13") (pin "12") (pinfunction "~{X}_12") (pintype "output"))
      (node (ref "E7") (pin "12") (pinfunction "I9_12") (pintype "passive"))
    )
    (net (code "75") (name "Net-(E10B-X)") (class "Default")
      (node (ref "E10") (pin "10") (pinfunction "X_10") (pintype "output"))
      (node (ref "E13") (pin "10") (pinfunction "X_10") (pintype "output"))
      (node (ref "E16") (pin "11") (pinfunction "I10_11") (pintype "passive"))
    )
    (net (code "76") (name "Net-(E10B-~{X})") (class "Default")
      (node (ref "E10") (pin "9") (pinfunction "~{X}_9") (pintype "output"))
      (node (ref "E13") (pin "9") (pinfunction "~{X}_9") (pintype "output"))
      (node (ref "E16") (pin "12") (pinfunction "I9_12") (pintype "passive"))
    )
    (net (code "77") (name "Net-(E12A-I6)") (class "Default")
      (node (ref "E12") (pin "3") (pinfunction "I6_3") (pintype "input"))
      (node (ref "E9") (pin "3") (pinfunction "O_3") (pintype "output"))
    )
    (net (code "78") (name "Net-(E12A-I8)") (class "Default")
      (node (ref "E12") (pin "9") (pinfunction "I8_9") (pintype "input"))
      (node (ref "E9") (pin "6") (pinfunction "O_6") (pintype "output"))
    )
    (net (code "79") (name "Net-(E18A-O)") (class "Default")
      (node (ref "E18") (pin "3") (pinfunction "O_3") (pintype "output"))
      (node (ref "R9") (pin "1") (pinfunction "1_1") (pintype "passive"))
      (node (ref "U$1") (pin "BJ2") (pinfunction "1_BJ2") (pintype "bidirectional"))
    )
    (net (code "80") (name "Net-(E18B-O)") (class "Default")
      (node (ref "E18") (pin "6") (pinfunction "O_6") (pintype "output"))
      (node (ref "R8") (pin "1") (pinfunction "1_1") (pintype "passive"))
      (node (ref "U$1") (pin "BU1") (pinfunction "1_BU1") (pintype "bidirectional"))
    )
    (net (code "81") (name "Net-(E18C-O)") (class "Default")
      (node (ref "E18") (pin "8") (pinfunction "O_8") (pintype "output"))
      (node (ref "R10") (pin "1") (pinfunction "1_1") (pintype "passive"))
      (node (ref "U$1") (pin "BD2") (pinfunction "1_BD2") (pintype "bidirectional"))
    )
    (net (code "82") (name "Net-(E18D-O)") (class "Default")
      (node (ref "E18") (pin "11") (pinfunction "O_11") (pintype "output"))
      (node (ref "R7") (pin "1") (pinfunction "1_1") (pintype "passive"))
      (node (ref "U$1") (pin "AB2") (pinfunction "1_AB2") (pintype "bidirectional"))
    )
    (net (code "83") (name "Net-(E19A-I9)") (class "Default")
      (node (ref "E19") (pin "12") (pinfunction "I9_12") (pintype "passive"))
      (node (ref "E20") (pin "12") (pinfunction "I9_12") (pintype "passive"))
    )
    (net (code "84") (name "Net-(E19A-I10)") (class "Default")
      (node (ref "E19") (pin "11") (pinfunction "I10_11") (pintype "passive"))
      (node (ref "E20") (pin "11") (pinfunction "I10_11") (pintype "passive"))
    )
    (net (code "85") (name "Net-(E21A-O)") (class "Default")
      (node (ref "E21") (pin "3") (pinfunction "O_3") (pintype "output"))
      (node (ref "R14") (pin "1") (pinfunction "1_1") (pintype "passive"))
      (node (ref "U$1") (pin "BR1") (pinfunction "1_BR1") (pintype "bidirectional"))
    )
    (net (code "86") (name "Net-(E21B-O)") (class "Default")
      (node (ref "E21") (pin "6") (pinfunction "O_6") (pintype "output"))
      (node (ref "R13") (pin "1") (pinfunction "1_1") (pintype "passive"))
      (node (ref "U$1") (pin "BR2") (pinfunction "1_BR2") (pintype "bidirectional"))
    )
    (net (code "87") (name "Net-(E21C-O)") (class "Default")
      (node (ref "E21") (pin "8") (pinfunction "O_8") (pintype "output"))
      (node (ref "R11") (pin "1") (pinfunction "1_1") (pintype "passive"))
      (node (ref "U$1") (pin "BF1") (pinfunction "1_BF1") (pintype "bidirectional"))
    )
    (net (code "88") (name "Net-(E21D-O)") (class "Default")
      (node (ref "E21") (pin "11") (pinfunction "O_11") (pintype "output"))
      (node (ref "R12") (pin "1") (pinfunction "1_1") (pintype "passive"))
      (node (ref "U$1") (pin "BS1") (pinfunction "1_BS1") (pintype "bidirectional"))
    )
    (net (code "89") (name "VCC") (class "Default")
      (node (ref "C1") (pin "1") (pinfunction "1_1") (pintype "passive"))
      (node (ref "C10") (pin "1") (pinfunction "1_1") (pintype "passive"))
      (node (ref "C11") (pin "1") (pinfunction "1_1") (pintype "passive"))
      (node (ref "C12") (pin "1") (pinfunction "1_1") (pintype "passive"))
      (node (ref "C13") (pin "1") (pinfunction "1_1") (pintype "passive"))
      (node (ref "C14") (pin "1") (pinfunction "1_1") (pintype "passive"))
      (node (ref "C15") (pin "1") (pinfunction "1_1") (pintype "passive"))
      (node (ref "C16") (pin "1") (pinfunction "1_1") (pintype "passive"))
      (node (ref "C17") (pin "1") (pinfunction "1_1") (pintype "passive"))
      (node (ref "C18") (pin "1") (pinfunction "1_1") (pintype "passive"))
      (node (ref "C19") (pin "1") (pinfunction "1_1") (pintype "passive"))
      (node (ref "C2") (pin "1") (pinfunction "1_1") (pintype "passive"))
      (node (ref "C20") (pin "1") (pinfunction "1_1") (pintype "passive"))
      (node (ref "C21") (pin "1") (pinfunction "1_1") (pintype "passive"))
      (node (ref "C3") (pin "1") (pinfunction "1_1") (pintype "passive"))
      (node (ref "C4") (pin "1") (pinfunction "1_1") (pintype "passive"))
      (node (ref "C5") (pin "1") (pinfunction "1_1") (pintype "passive"))
      (node (ref "C6") (pin "1") (pinfunction "1_1") (pintype "passive"))
      (node (ref "C7") (pin "1") (pinfunction "1_1") (pintype "passive"))
      (node (ref "C8") (pin "1") (pinfunction "1_1") (pintype "passive"))
      (node (ref "C9") (pin "1") (pinfunction "1_1") (pintype "passive"))
      (node (ref "R1") (pin "2") (pinfunction "2_2") (pintype "passive"))
      (node (ref "R10") (pin "2") (pinfunction "2_2") (pintype "passive"))
      (node (ref "R11") (pin "2") (pinfunction "2_2") (pintype "passive"))
      (node (ref "R12") (pin "2") (pinfunction "2_2") (pintype "passive"))
      (node (ref "R13") (pin "2") (pinfunction "2_2") (pintype "passive"))
      (node (ref "R14") (pin "2") (pinfunction "2_2") (pintype "passive"))
      (node (ref "R2") (pin "2") (pinfunction "2_2") (pintype "passive"))
      (node (ref "R3") (pin "2") (pinfunction "2_2") (pintype "passive"))
      (node (ref "R4") (pin "2") (pinfunction "2_2") (pintype "passive"))
      (node (ref "R5") (pin "2") (pinfunction "2_2") (pintype "passive"))
      (node (ref "R6") (pin "2") (pinfunction "2_2") (pintype "passive"))
      (node (ref "R7") (pin "2") (pinfunction "2_2") (pintype "passive"))
      (node (ref "R8") (pin "2") (pinfunction "2_2") (pintype "passive"))
      (node (ref "R9") (pin "2") (pinfunction "2_2") (pintype "passive"))
      (node (ref "U$1") (pin "AA2") (pinfunction "1_AA2") (pintype "bidirectional"))
      (node (ref "U$1") (pin "BA2") (pinfunction "1_BA2") (pintype "bidirectional"))
    )
    (net (code "90") (name "unconnected-(E2A-I9-Pad12)") (class "Default")
      (node (ref "E2") (pin "12") (pinfunction "I9_12") (pintype "passive"))
    )
    (net (code "91") (name "unconnected-(E2A-I10-Pad11)") (class "Default")
      (node (ref "E2") (pin "11") (pinfunction "I10_11") (pintype "passive"))
    )
    (net (code "92") (name "unconnected-(E3A-I9-Pad12)") (class "Default")
      (node (ref "E3") (pin "12") (pinfunction "I9_12") (pintype "passive"))
    )
    (net (code "93") (name "unconnected-(E3A-I10-Pad11)") (class "Default")
      (node (ref "E3") (pin "11") (pinfunction "I10_11") (pintype "passive"))
    )
    (net (code "94") (name "unconnected-(E6A-I9-Pad12)") (class "Default")
      (node (ref "E6") (pin "12") (pinfunction "I9_12") (pintype "passive"))
    )
    (net (code "95") (name "unconnected-(E6A-I10-Pad11)") (class "Default")
      (node (ref "E6") (pin "11") (pinfunction "I10_11") (pintype "passive"))
    )
    (net (code "96") (name "unconnected-(E8A-CLR-Pad1)") (class "Default")
      (node (ref "E8") (pin "1") (pinfunction "CLR_1") (pintype "input"))
    )
    (net (code "97") (name "unconnected-(E8A-PRE-Pad4)") (class "Default")
      (node (ref "E8") (pin "4") (pinfunction "PRE_4") (pintype "input"))
    )
    (net (code "98") (name "unconnected-(E8B-CLR-Pad13)") (class "Default")
      (node (ref "E8") (pin "13") (pinfunction "CLR_13") (pintype "input"))
    )
    (net (code "99") (name "unconnected-(E8B-PRE-Pad10)") (class "Default")
      (node (ref "E8") (pin "10") (pinfunction "PRE_10") (pintype "input"))
    )
    (net (code "100") (name "unconnected-(E11A-CLR-Pad1)") (class "Default")
      (node (ref "E11") (pin "1") (pinfunction "CLR_1") (pintype "input"))
    )
    (net (code "101") (name "unconnected-(E11A-PRE-Pad4)") (class "Default")
      (node (ref "E11") (pin "4") (pinfunction "PRE_4") (pintype "input"))
    )
    (net (code "102") (name "unconnected-(E11B-CLR-Pad13)") (class "Default")
      (node (ref "E11") (pin "13") (pinfunction "CLR_13") (pintype "input"))
    )
    (net (code "103") (name "unconnected-(E11B-PRE-Pad10)") (class "Default")
      (node (ref "E11") (pin "10") (pinfunction "PRE_10") (pintype "input"))
    )
    (net (code "104") (name "unconnected-(E12A-I9-Pad12)") (class "Default")
      (node (ref "E12") (pin "12") (pinfunction "I9_12") (pintype "passive"))
    )
    (net (code "105") (name "unconnected-(E12A-I10-Pad11)") (class "Default")
      (node (ref "E12") (pin "11") (pinfunction "I10_11") (pintype "passive"))
    )
    (net (code "106") (name "unconnected-(E14A-CLR-Pad1)") (class "Default")
      (node (ref "E14") (pin "1") (pinfunction "CLR_1") (pintype "input"))
    )
    (net (code "107") (name "unconnected-(E14A-PRE-Pad4)") (class "Default")
      (node (ref "E14") (pin "4") (pinfunction "PRE_4") (pintype "input"))
    )
    (net (code "108") (name "unconnected-(E14B-CLR-Pad13)") (class "Default")
      (node (ref "E14") (pin "13") (pinfunction "CLR_13") (pintype "input"))
    )
    (net (code "109") (name "unconnected-(E14B-PRE-Pad10)") (class "Default")
      (node (ref "E14") (pin "10") (pinfunction "PRE_10") (pintype "input"))
    )
    (net (code "110") (name "unconnected-(E15A-I9-Pad12)") (class "Default")
      (node (ref "E15") (pin "12") (pinfunction "I9_12") (pintype "passive"))
    )
    (net (code "111") (name "unconnected-(E15A-I10-Pad11)") (class "Default")
      (node (ref "E15") (pin "11") (pinfunction "I10_11") (pintype "passive"))
    )
    (net (code "112") (name "unconnected-(E17A-CLR-Pad1)") (class "Default")
      (node (ref "E17") (pin "1") (pinfunction "CLR_1") (pintype "input"))
    )
    (net (code "113") (name "unconnected-(E17A-PRE-Pad4)") (class "Default")
      (node (ref "E17") (pin "4") (pinfunction "PRE_4") (pintype "input"))
    )
    (net (code "114") (name "unconnected-(E17B-CLR-Pad13)") (class "Default")
      (node (ref "E17") (pin "13") (pinfunction "CLR_13") (pintype "input"))
    )
    (net (code "115") (name "unconnected-(E17B-PRE-Pad10)") (class "Default")
      (node (ref "E17") (pin "10") (pinfunction "PRE_10") (pintype "input"))
    )
  )
)
